# PCB.net
KiCad netlist of a schematic drawn in EAGLE
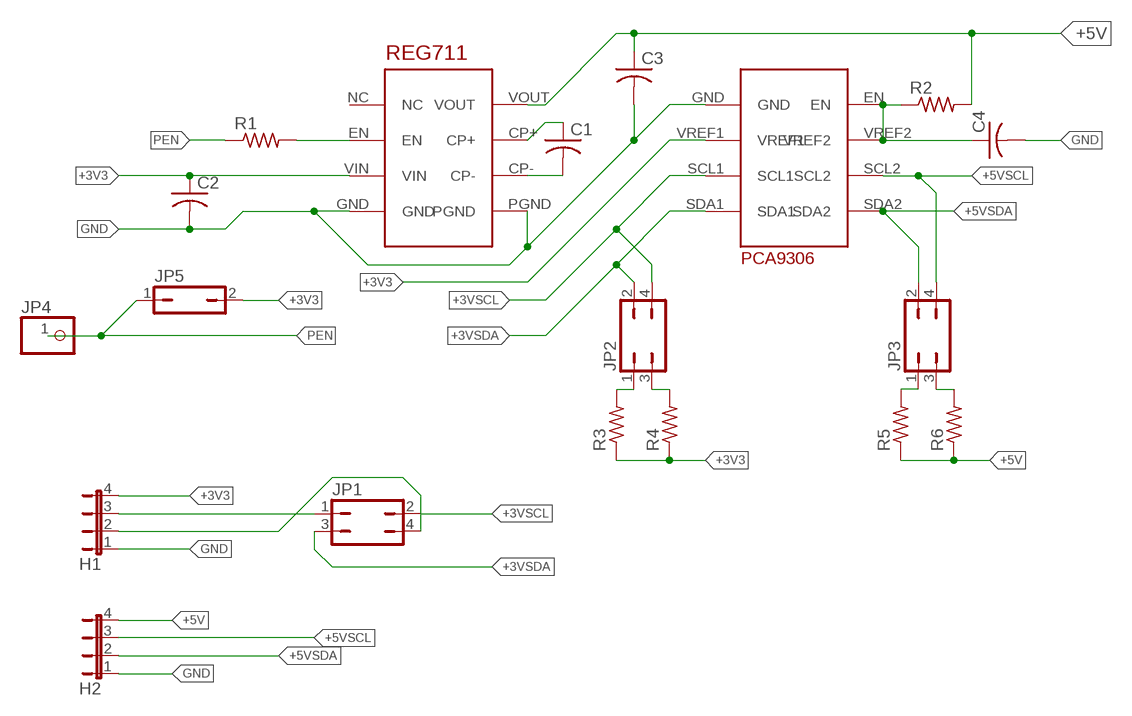
[diagram p0: schematic, sheet 1]

(export (version "E")
  (design (tool "Eeschema 10.0.6"))
  (components
    (comp (ref "C1")
      (value "C-USC1206")
      (footprint "eagle-import:C1206")
      (libsource (lib "eagle-import") (part "C-USC1206"))
    )
    (comp (ref "C2")
      (value "C-USC1206")
      (footprint "eagle-import:C1206")
      (libsource (lib "eagle-import") (part "C-USC1206"))
    )
    (comp (ref "C3")
      (value "C-USC1206")
      (footprint "eagle-import:C1206")
      (libsource (lib "eagle-import") (part "C-USC1206"))
    )
    (comp (ref "C4")
      (value "C-USC1206")
      (footprint "eagle-import:C1206")
      (libsource (lib "eagle-import") (part "C-USC1206"))
    )
    (comp (ref "H1")
      (value "JP4E")
      (footprint "eagle-import:JP4")
      (libsource (lib "eagle-import") (part "JP4E"))
    )
    (comp (ref "H2")
      (value "JP4E")
      (footprint "eagle-import:JP4")
      (libsource (lib "eagle-import") (part "JP4E"))
    )
    (comp (ref "JP1")
      (value "JP2Q")
      (footprint "eagle-import:JP2Q")
      (libsource (lib "eagle-import") (part "JP2Q"))
    )
    (comp (ref "JP2")
      (value "JP2Q")
      (footprint "eagle-import:JP2Q")
      (libsource (lib "eagle-import") (part "JP2Q"))
    )
    (comp (ref "JP3")
      (value "JP2Q")
      (footprint "eagle-import:JP2Q")
      (libsource (lib "eagle-import") (part "JP2Q"))
    )
    (comp (ref "JP4")
      (value "PINHD-1X1")
      (footprint "eagle-import:1X01")
      (libsource (lib "eagle-import") (part "PINHD-1X1"))
    )
    (comp (ref "JP5")
      (value "JP1Q")
      (footprint "eagle-import:JP1")
      (libsource (lib "eagle-import") (part "JP1Q"))
    )
    (comp (ref "PCA9306")
      (value "PCA9306")
      (footprint "eagle-import:PCA9306")
      (libsource (lib "eagle-import") (part "PCA9306"))
    )
    (comp (ref "R1")
      (value "R-US_0204/2V")
      (footprint "eagle-import:0204V")
      (libsource (lib "eagle-import") (part "R-US_0204/2V"))
    )
    (comp (ref "R2")
      (value "R-US_0204/2V")
      (footprint "eagle-import:0204V")
      (libsource (lib "eagle-import") (part "R-US_0204/2V"))
    )
    (comp (ref "R3")
      (value "R-US_0204/2V")
      (footprint "eagle-import:0204V")
      (libsource (lib "eagle-import") (part "R-US_0204/2V"))
    )
    (comp (ref "R4")
      (value "R-US_0204/2V")
      (footprint "eagle-import:0204V")
      (libsource (lib "eagle-import") (part "R-US_0204/2V"))
    )
    (comp (ref "R5")
      (value "R-US_0204/2V")
      (footprint "eagle-import:0204V")
      (libsource (lib "eagle-import") (part "R-US_0204/2V"))
    )
    (comp (ref "R6")
      (value "R-US_0204/2V")
      (footprint "eagle-import:0204V")
      (libsource (lib "eagle-import") (part "R-US_0204/2V"))
    )
    (comp (ref "REG711")
      (value "REG711")
      (footprint "eagle-import:REG711")
      (libsource (lib "eagle-import") (part "REG711"))
    )
  )
  (nets
    (net (code "1") (name "+3V3") (class "Default")
      (node (ref "C2") (pin "1") (pinfunction "1_1") (pintype "passive"))
      (node (ref "H1") (pin "4") (pinfunction "4_4") (pintype "passive"))
      (node (ref "JP5") (pin "2") (pinfunction "2_2") (pintype "passive"))
      (node (ref "PCA9306") (pin "VREF1") (pinfunction "VREF1_VREF1") (pintype "bidirectional"))
      (node (ref "R3") (pin "1") (pinfunction "1_1") (pintype "passive"))
      (node (ref "R4") (pin "1") (pinfunction "1_1") (pintype "passive"))
      (node (ref "REG711") (pin "VIN") (pinfunction "VIN_VIN") (pintype "bidirectional"))
    )
    (net (code "2") (name "+3VSCL") (class "Default")
      (node (ref "JP1") (pin "2") (pinfunction "2_2") (pintype "passive"))
      (node (ref "JP2") (pin "4") (pinfunction "4_4") (pintype "passive"))
      (node (ref "PCA9306") (pin "SCL1") (pinfunction "SCL1_SCL1") (pintype "bidirectional"))
    )
    (net (code "3") (name "+3VSDA") (class "Default")
      (node (ref "JP1") (pin "3") (pinfunction "3_3") (pintype "passive"))
      (node (ref "JP2") (pin "2") (pinfunction "2_2") (pintype "passive"))
      (node (ref "PCA9306") (pin "SDA1") (pinfunction "SDA1_SDA1") (pintype "bidirectional"))
    )
    (net (code "4") (name "+5V") (class "Default")
      (node (ref "C3") (pin "1") (pinfunction "1_1") (pintype "passive"))
      (node (ref "C4") (pin "1") (pinfunction "1_1") (pintype "passive"))
      (node (ref "H2") (pin "4") (pinfunction "4_4") (pintype "passive"))
      (node (ref "PCA9306") (pin "EN") (pinfunction "EN_EN") (pintype "bidirectional"))
      (node (ref "PCA9306") (pin "VREF2") (pinfunction "VREF2_VREF2") (pintype "bidirectional"))
      (node (ref "R2") (pin "1") (pinfunction "1_1") (pintype "passive"))
      (node (ref "R2") (pin "2") (pinfunction "2_2") (pintype "passive"))
      (node (ref "R5") (pin "1") (pinfunction "1_1") (pintype "passive"))
      (node (ref "R6") (pin "1") (pinfunction "1_1") (pintype "passive"))
      (node (ref "REG711") (pin "VOUT") (pinfunction "VOUT_VOUT") (pintype "bidirectional"))
    )
    (net (code "5") (name "+5VSCL") (class "Default")
      (node (ref "H2") (pin "3") (pinfunction "3_3") (pintype "passive"))
      (node (ref "JP3") (pin "4") (pinfunction "4_4") (pintype "passive"))
      (node (ref "PCA9306") (pin "SCL2") (pinfunction "SCL2_SCL2") (pintype "bidirectional"))
    )
    (net (code "6") (name "+5VSDA") (class "Default")
      (node (ref "H2") (pin "2") (pinfunction "2_2") (pintype "passive"))
      (node (ref "JP3") (pin "2") (pinfunction "2_2") (pintype "passive"))
      (node (ref "PCA9306") (pin "SDA2") (pinfunction "SDA2_SDA2") (pintype "bidirectional"))
    )
    (net (code "7") (name "GND") (class "Default")
      (node (ref "C2") (pin "2") (pinfunction "2_2") (pintype "passive"))
      (node (ref "C3") (pin "2") (pinfunction "2_2") (pintype "passive"))
      (node (ref "C4") (pin "2") (pinfunction "2_2") (pintype "passive"))
      (node (ref "H1") (pin "1") (pinfunction "1_1") (pintype "passive"))
      (node (ref "H2") (pin "1") (pinfunction "1_1") (pintype "passive"))
      (node (ref "PCA9306") (pin "GND") (pinfunction "GND_GND") (pintype "bidirectional"))
      (node (ref "REG711") (pin "GND") (pinfunction "GND_GND") (pintype "bidirectional"))
      (node (ref "REG711") (pin "PGND") (pinfunction "PGND_PGND") (pintype "bidirectional"))
    )
    (net (code "8") (name "Net-(C1-Pad1)") (class "Default")
      (node (ref "C1") (pin "1") (pinfunction "1_1") (pintype "passive"))
      (node (ref "REG711") (pin "CP+") (pinfunction "CP+_CP+") (pintype "bidirectional"))
    )
    (net (code "9") (name "Net-(C1-Pad2)") (class "Default")
      (node (ref "C1") (pin "2") (pinfunction "2_2") (pintype "passive"))
      (node (ref "REG711") (pin "CP-") (pinfunction "CP-_CP-") (pintype "bidirectional"))
    )
    (net (code "10") (name "Net-(H1-Pad2)") (class "Default")
      (node (ref "H1") (pin "2") (pinfunction "2_2") (pintype "passive"))
      (node (ref "JP1") (pin "4") (pinfunction "4_4") (pintype "passive"))
    )
    (net (code "11") (name "Net-(H1-Pad3)") (class "Default")
      (node (ref "H1") (pin "3") (pinfunction "3_3") (pintype "passive"))
      (node (ref "JP1") (pin "1") (pinfunction "1_1") (pintype "passive"))
    )
    (net (code "12") (name "Net-(JP2-Pad1)") (class "Default")
      (node (ref "JP2") (pin "1") (pinfunction "1_1") (pintype "passive"))
      (node (ref "R3") (pin "2") (pinfunction "2_2") (pintype "passive"))
    )
    (net (code "13") (name "Net-(JP2-Pad3)") (class "Default")
      (node (ref "JP2") (pin "3") (pinfunction "3_3") (pintype "passive"))
      (node (ref "R4") (pin "2") (pinfunction "2_2") (pintype "passive"))
    )
    (net (code "14") (name "Net-(JP3-Pad1)") (class "Default")
      (node (ref "JP3") (pin "1") (pinfunction "1_1") (pintype "passive"))
      (node (ref "R5") (pin "2") (pinfunction "2_2") (pintype "passive"))
    )
    (net (code "15") (name "Net-(JP3-Pad3)") (class "Default")
      (node (ref "JP3") (pin "3") (pinfunction "3_3") (pintype "passive"))
      (node (ref "R6") (pin "2") (pinfunction "2_2") (pintype "passive"))
    )
    (net (code "16") (name "Net-(R1-Pad2)") (class "Default")
      (node (ref "R1") (pin "2") (pinfunction "2_2") (pintype "passive"))
      (node (ref "REG711") (pin "EN") (pinfunction "EN_EN") (pintype "bidirectional"))
    )
    (net (code "17") (name "PEN") (class "Default")
      (node (ref "JP4") (pin "1") (pinfunction "1_1") (pintype "passive"))
      (node (ref "JP5") (pin "1") (pinfunction "1_1") (pintype "passive"))
      (node (ref "R1") (pin "1") (pinfunction "1_1") (pintype "passive"))
    )
    (net (code "18") (name "unconnected-(REG711-PadNC)") (class "Default")
      (node (ref "REG711") (pin "NC") (pinfunction "NC_NC") (pintype "bidirectional"))
    )
  )
)
